# PowerDomains.net
KiCad netlist of a schematic drawn in Altium Designer
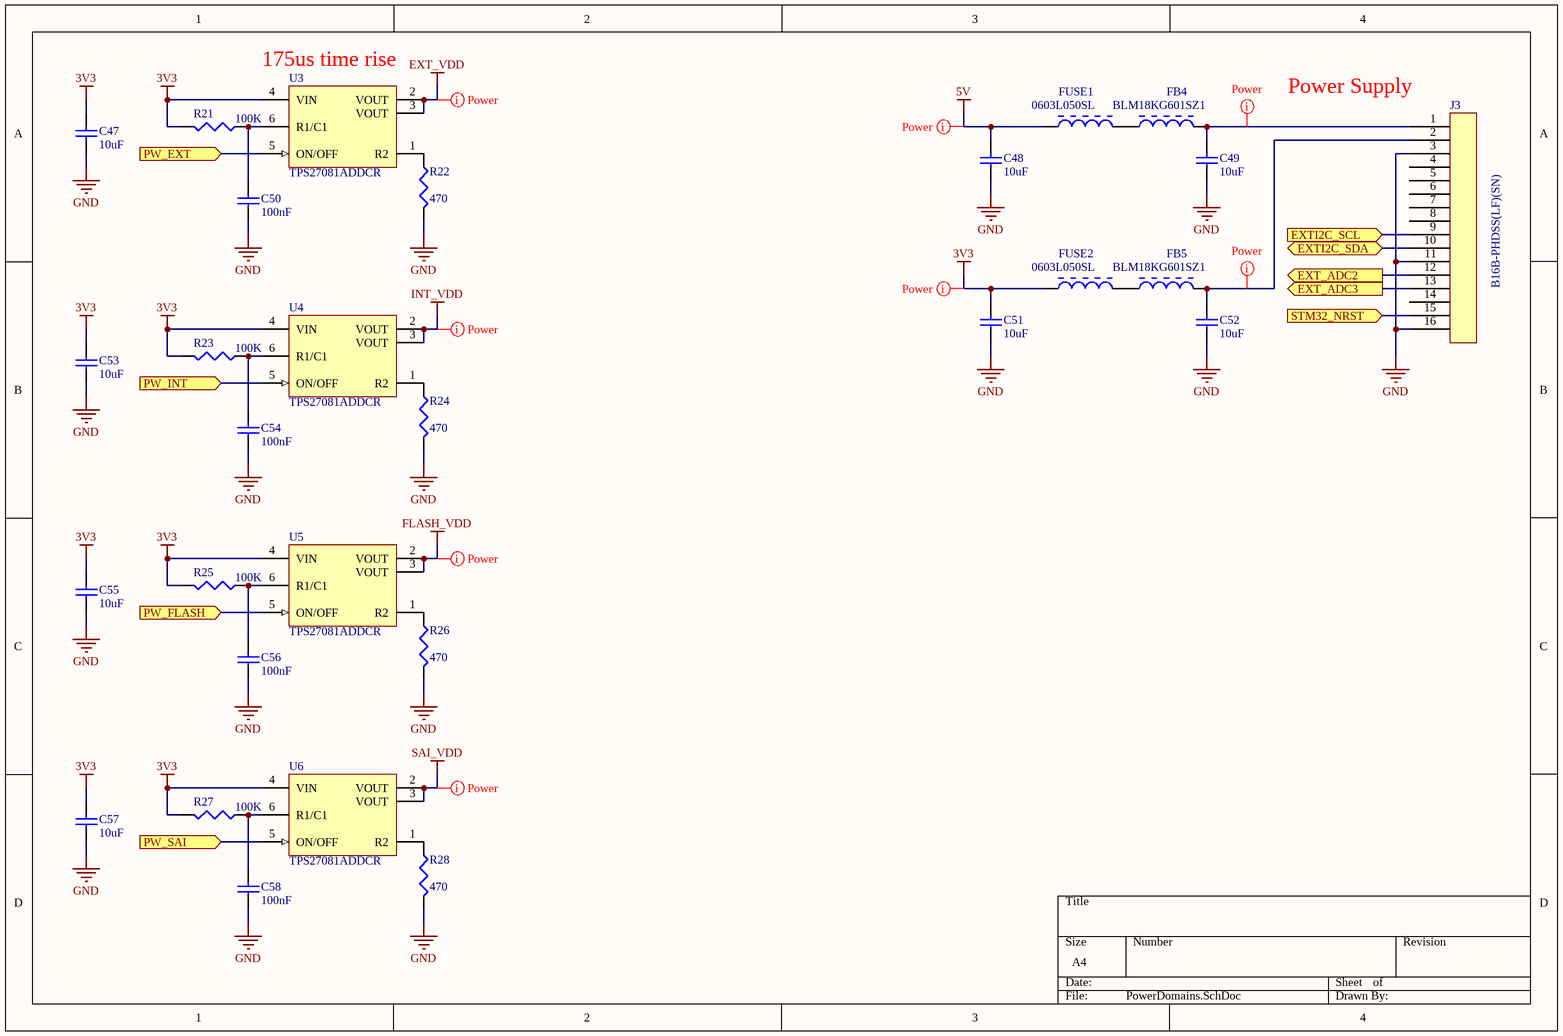
[diagram p0: PowerDomains.SchDoc]

(export (version "E")
  (design (tool "Eeschema 10.0.6"))
  (components
    (comp (ref "C47")
      (value "10uF")
      (footprint "CAPC1608X90X35NL10T15")
      (fields (field (name "PART NUMBER") "GRM188R71H102KA01D") (field (name "MANUFACTURER") "Murata"))
      (libsource (lib "Altium Content Vault") (part "CAP"))
    )
    (comp (ref "C48")
      (value "10uF")
      (footprint "CAPC1608X90X35NL10T15")
      (fields (field (name "PART NUMBER") "GRM188R71H102KA01D") (field (name "MANUFACTURER") "Murata"))
      (libsource (lib "Altium Content Vault") (part "CAP"))
    )
    (comp (ref "C49")
      (value "10uF")
      (footprint "CAPC1608X90X35NL10T15")
      (fields (field (name "PART NUMBER") "GRM188R71H102KA01D") (field (name "MANUFACTURER") "Murata"))
      (libsource (lib "Altium Content Vault") (part "CAP"))
    )
    (comp (ref "C50")
      (value "100nF")
      (footprint "CAPC1608X90X35NL10T15")
      (fields (field (name "PART NUMBER") "GRM188R71H102KA01D") (field (name "MANUFACTURER") "Murata"))
      (libsource (lib "Altium Content Vault") (part "CAP"))
    )
    (comp (ref "C51")
      (value "10uF")
      (footprint "CAPC1608X90X35NL10T15")
      (fields (field (name "PART NUMBER") "GRM188R71H102KA01D") (field (name "MANUFACTURER") "Murata"))
      (libsource (lib "Altium Content Vault") (part "CAP"))
    )
    (comp (ref "C52")
      (value "10uF")
      (footprint "CAPC1608X90X35NL10T15")
      (fields (field (name "PART NUMBER") "GRM188R71H102KA01D") (field (name "MANUFACTURER") "Murata"))
      (libsource (lib "Altium Content Vault") (part "CAP"))
    )
    (comp (ref "C53")
      (value "10uF")
      (footprint "CAPC1608X90X35NL10T15")
      (fields (field (name "PART NUMBER") "GRM188R71H102KA01D") (field (name "MANUFACTURER") "Murata"))
      (libsource (lib "Altium Content Vault") (part "CAP"))
    )
    (comp (ref "C54")
      (value "100nF")
      (footprint "CAPC1608X90X35NL10T15")
      (fields (field (name "PART NUMBER") "GRM188R71H102KA01D") (field (name "MANUFACTURER") "Murata"))
      (libsource (lib "Altium Content Vault") (part "CAP"))
    )
    (comp (ref "C55")
      (value "10uF")
      (footprint "CAPC1608X90X35NL10T15")
      (fields (field (name "PART NUMBER") "GRM188R71H102KA01D") (field (name "MANUFACTURER") "Murata"))
      (libsource (lib "Altium Content Vault") (part "CAP"))
    )
    (comp (ref "C56")
      (value "100nF")
      (footprint "CAPC1608X90X35NL10T15")
      (fields (field (name "PART NUMBER") "GRM188R71H102KA01D") (field (name "MANUFACTURER") "Murata"))
      (libsource (lib "Altium Content Vault") (part "CAP"))
    )
    (comp (ref "C57")
      (value "10uF")
      (footprint "CAPC1608X90X35NL10T15")
      (fields (field (name "PART NUMBER") "GRM188R71H102KA01D") (field (name "MANUFACTURER") "Murata"))
      (libsource (lib "Altium Content Vault") (part "CAP"))
    )
    (comp (ref "C58")
      (value "100nF")
      (footprint "CAPC1608X90X35NL10T15")
      (fields (field (name "PART NUMBER") "GRM188R71H102KA01D") (field (name "MANUFACTURER") "Murata"))
      (libsource (lib "Altium Content Vault") (part "CAP"))
    )
    (comp (ref "FB4")
      (value "BLM18KG601SZ1")
      (footprint "MURA-BLM18SG-B25-CHIP-2_V1")
      (fields (field (name "MANUFACTURER") "Murata") (field (name "PARTNUMBER") "BLM18SG221TN1D"))
      (libsource (lib "Altium Content Vault") (part "MURA-FB-2"))
    )
    (comp (ref "FB5")
      (value "BLM18KG601SZ1")
      (footprint "MURA-BLM18SG-B25-CHIP-2_V1")
      (fields (field (name "MANUFACTURER") "Murata") (field (name "PARTNUMBER") "BLM18SG221TN1D"))
      (libsource (lib "Altium Content Vault") (part "MURA-FB-2"))
    )
    (comp (ref "FUSE1")
      (value "0603L050SL")
      (footprint "MURA-BLM18SG-B25-CHIP-2_V1")
      (fields (field (name "MANUFACTURER") "Murata") (field (name "PARTNUMBER") "BLM18SG221TN1D"))
      (libsource (lib "Altium Content Vault") (part "MURA-FB-2"))
    )
    (comp (ref "FUSE2")
      (value "0603L050SL")
      (footprint "MURA-BLM18SG-B25-CHIP-2_V1")
      (fields (field (name "MANUFACTURER") "Murata") (field (name "PARTNUMBER") "BLM18SG221TN1D"))
      (libsource (lib "Altium Content Vault") (part "MURA-FB-2"))
    )
    (comp (ref "J3")
      (value "B16B-PHDSS(LF)(SN)")
      (footprint "B16B-PHDSS(LF)(SN) - duplicate")
      (libsource (lib "STM32WB55RGV7") (part "B16B-PHDSS(LF)(SN)"))
    )
    (comp (ref "R21")
      (value "100K")
      (footprint "J1-0603")
      (description "Resistor")
      (fields (field (name "PUBLISHER") "Altium Limited"))
      (libsource (lib "Miscellaneous Devices") (part "Res3"))
    )
    (comp (ref "R22")
      (value "470")
      (footprint "J1-0603")
      (description "Resistor")
      (fields (field (name "PUBLISHER") "Altium Limited"))
      (libsource (lib "Miscellaneous Devices") (part "Res3"))
    )
    (comp (ref "R23")
      (value "100K")
      (footprint "J1-0603")
      (description "Resistor")
      (fields (field (name "PUBLISHER") "Altium Limited"))
      (libsource (lib "Miscellaneous Devices") (part "Res3"))
    )
    (comp (ref "R24")
      (value "470")
      (footprint "J1-0603")
      (description "Resistor")
      (fields (field (name "PUBLISHER") "Altium Limited"))
      (libsource (lib "Miscellaneous Devices") (part "Res3"))
    )
    (comp (ref "R25")
      (value "100K")
      (footprint "J1-0603")
      (description "Resistor")
      (fields (field (name "PUBLISHER") "Altium Limited"))
      (libsource (lib "Miscellaneous Devices") (part "Res3"))
    )
    (comp (ref "R26")
      (value "470")
      (footprint "J1-0603")
      (description "Resistor")
      (fields (field (name "PUBLISHER") "Altium Limited"))
      (libsource (lib "Miscellaneous Devices") (part "Res3"))
    )
    (comp (ref "R27")
      (value "100K")
      (footprint "J1-0603")
      (description "Resistor")
      (fields (field (name "PUBLISHER") "Altium Limited"))
      (libsource (lib "Miscellaneous Devices") (part "Res3"))
    )
    (comp (ref "R28")
      (value "470")
      (footprint "J1-0603")
      (description "Resistor")
      (fields (field (name "PUBLISHER") "Altium Limited"))
      (libsource (lib "Miscellaneous Devices") (part "Res3"))
    )
    (comp (ref "U3")
      (value "TPS27081ADDCR")
      (footprint "DDC0006A_L")
      (fields (field (name "PARTNUMBER") "TPS27081A") (field (name "MANUFACTURER") "Texas Instruments"))
      (libsource (lib "Altium Content Vault") (part "TI-TPS27081A-DDC-6"))
    )
    (comp (ref "U4")
      (value "TPS27081ADDCR")
      (footprint "DDC0006A_L")
      (fields (field (name "PARTNUMBER") "TPS27081A") (field (name "MANUFACTURER") "Texas Instruments"))
      (libsource (lib "Altium Content Vault") (part "TI-TPS27081A-DDC-6"))
    )
    (comp (ref "U5")
      (value "TPS27081ADDCR")
      (footprint "DDC0006A_L")
      (fields (field (name "PARTNUMBER") "TPS27081A") (field (name "MANUFACTURER") "Texas Instruments"))
      (libsource (lib "Altium Content Vault") (part "TI-TPS27081A-DDC-6"))
    )
    (comp (ref "U6")
      (value "TPS27081ADDCR")
      (footprint "DDC0006A_L")
      (fields (field (name "PARTNUMBER") "TPS27081A") (field (name "MANUFACTURER") "Texas Instruments"))
      (libsource (lib "Altium Content Vault") (part "TI-TPS27081A-DDC-6"))
    )
  )
  (nets
    (net (code "1") (name "/EXTI2C_SCL") (class "Default") (node (ref "J3") (pin "9") (pintype "passive")))
    (net (code "2") (name "/EXTI2C_SDA") (class "Default") (node (ref "J3") (pin "10") (pintype "passive")))
    (net (code "3") (name "/EXT_ADC2") (class "Default") (node (ref "J3") (pin "12") (pintype "passive")))
    (net (code "4") (name "/EXT_ADC3") (class "Default") (node (ref "J3") (pin "13") (pintype "passive")))
    (net (code "5") (name "/PW_EXT") (class "Default")
      (node (ref "U3") (pin "5") (pinfunction "ON/OFF_5") (pintype "input"))
    )
    (net (code "6") (name "/PW_FLASH") (class "Default")
      (node (ref "U5") (pin "5") (pinfunction "ON/OFF_5") (pintype "input"))
    )
    (net (code "7") (name "/PW_INT") (class "Default")
      (node (ref "U4") (pin "5") (pinfunction "ON/OFF_5") (pintype "input"))
    )
    (net (code "8") (name "/PW_SAI") (class "Default")
      (node (ref "U6") (pin "5") (pinfunction "ON/OFF_5") (pintype "input"))
    )
    (net (code "9") (name "/STM32_NRST") (class "Default") (node (ref "J3") (pin "15") (pintype "passive")))
    (net (code "10") (name "3V3") (class "Default")
      (node (ref "C47") (pin "2") (pinfunction "2_2") (pintype "passive"))
      (node (ref "C51") (pin "2") (pinfunction "2_2") (pintype "passive"))
      (node (ref "C53") (pin "2") (pinfunction "2_2") (pintype "passive"))
      (node (ref "C55") (pin "2") (pinfunction "2_2") (pintype "passive"))
      (node (ref "C57") (pin "2") (pinfunction "2_2") (pintype "passive"))
      (node (ref "FUSE2") (pin "1") (pinfunction "1_1") (pintype "passive"))
      (node (ref "R21") (pin "2") (pinfunction "2_2") (pintype "passive"))
      (node (ref "R23") (pin "2") (pinfunction "2_2") (pintype "passive"))
      (node (ref "R25") (pin "2") (pinfunction "2_2") (pintype "passive"))
      (node (ref "R27") (pin "2") (pinfunction "2_2") (pintype "passive"))
      (node (ref "U3") (pin "4") (pinfunction "VIN_4") (pintype "power_in"))
      (node (ref "U4") (pin "4") (pinfunction "VIN_4") (pintype "power_in"))
      (node (ref "U5") (pin "4") (pinfunction "VIN_4") (pintype "power_in"))
      (node (ref "U6") (pin "4") (pinfunction "VIN_4") (pintype "power_in"))
    )
    (net (code "11") (name "5V") (class "Default")
      (node (ref "C48") (pin "2") (pinfunction "2_2") (pintype "passive"))
      (node (ref "FUSE1") (pin "1") (pinfunction "1_1") (pintype "passive"))
    )
    (net (code "12") (name "EXT_VDD") (class "Default")
      (node (ref "U3") (pin "2") (pinfunction "VOUT_2") (pintype "power_in"))
      (node (ref "U3") (pin "3") (pinfunction "VOUT_3") (pintype "power_in"))
    )
    (net (code "13") (name "FLASH_VDD") (class "Default")
      (node (ref "U5") (pin "2") (pinfunction "VOUT_2") (pintype "power_in"))
      (node (ref "U5") (pin "3") (pinfunction "VOUT_3") (pintype "power_in"))
    )
    (net (code "14") (name "GND") (class "Default")
      (node (ref "C47") (pin "1") (pinfunction "1_1") (pintype "passive"))
      (node (ref "C48") (pin "1") (pinfunction "1_1") (pintype "passive"))
      (node (ref "C49") (pin "1") (pinfunction "1_1") (pintype "passive"))
      (node (ref "C50") (pin "1") (pinfunction "1_1") (pintype "passive"))
      (node (ref "C51") (pin "1") (pinfunction "1_1") (pintype "passive"))
      (node (ref "C52") (pin "1") (pinfunction "1_1") (pintype "passive"))
      (node (ref "C53") (pin "1") (pinfunction "1_1") (pintype "passive"))
      (node (ref "C54") (pin "1") (pinfunction "1_1") (pintype "passive"))
      (node (ref "C55") (pin "1") (pinfunction "1_1") (pintype "passive"))
      (node (ref "C56") (pin "1") (pinfunction "1_1") (pintype "passive"))
      (node (ref "C57") (pin "1") (pinfunction "1_1") (pintype "passive"))
      (node (ref "C58") (pin "1") (pinfunction "1_1") (pintype "passive"))
      (node (ref "J3") (pin "11") (pintype "passive"))
      (node (ref "J3") (pin "16") (pintype "passive"))
      (node (ref "J3") (pin "3") (pintype "passive"))
      (node (ref "R22") (pin "2") (pinfunction "2_2") (pintype "passive"))
      (node (ref "R24") (pin "2") (pinfunction "2_2") (pintype "passive"))
      (node (ref "R26") (pin "2") (pinfunction "2_2") (pintype "passive"))
      (node (ref "R28") (pin "2") (pinfunction "2_2") (pintype "passive"))
    )
    (net (code "15") (name "INT_VDD") (class "Default")
      (node (ref "U4") (pin "2") (pinfunction "VOUT_2") (pintype "power_in"))
      (node (ref "U4") (pin "3") (pinfunction "VOUT_3") (pintype "power_in"))
    )
    (net (code "16") (name "Net-(C49-Pad2)") (class "Default")
      (node (ref "C49") (pin "2") (pinfunction "2_2") (pintype "passive"))
      (node (ref "FB4") (pin "2") (pinfunction "2_2") (pintype "passive"))
      (node (ref "J3") (pin "1") (pintype "passive"))
    )
    (net (code "17") (name "Net-(C52-Pad2)") (class "Default")
      (node (ref "C52") (pin "2") (pinfunction "2_2") (pintype "passive"))
      (node (ref "FB5") (pin "2") (pinfunction "2_2") (pintype "passive"))
      (node (ref "J3") (pin "2") (pintype "passive"))
    )
    (net (code "18") (name "Net-(FB4-Pad1)") (class "Default")
      (node (ref "FB4") (pin "1") (pinfunction "1_1") (pintype "passive"))
      (node (ref "FUSE1") (pin "2") (pinfunction "2_2") (pintype "passive"))
    )
    (net (code "19") (name "Net-(FB5-Pad1)") (class "Default")
      (node (ref "FB5") (pin "1") (pinfunction "1_1") (pintype "passive"))
      (node (ref "FUSE2") (pin "2") (pinfunction "2_2") (pintype "passive"))
    )
    (net (code "20") (name "Net-(U3-R1{slash}C1)") (class "Default")
      (node (ref "C50") (pin "2") (pinfunction "2_2") (pintype "passive"))
      (node (ref "R21") (pin "1") (pinfunction "1_1") (pintype "passive"))
      (node (ref "U3") (pin "6") (pinfunction "R1/C1_6") (pintype "passive"))
    )
    (net (code "21") (name "Net-(U3-R2)") (class "Default")
      (node (ref "R22") (pin "1") (pinfunction "1_1") (pintype "passive"))
      (node (ref "U3") (pin "1") (pinfunction "R2_1") (pintype "passive"))
    )
    (net (code "22") (name "Net-(U4-R1{slash}C1)") (class "Default")
      (node (ref "C54") (pin "2") (pinfunction "2_2") (pintype "passive"))
      (node (ref "R23") (pin "1") (pinfunction "1_1") (pintype "passive"))
      (node (ref "U4") (pin "6") (pinfunction "R1/C1_6") (pintype "passive"))
    )
    (net (code "23") (name "Net-(U4-R2)") (class "Default")
      (node (ref "R24") (pin "1") (pinfunction "1_1") (pintype "passive"))
      (node (ref "U4") (pin "1") (pinfunction "R2_1") (pintype "passive"))
    )
    (net (code "24") (name "Net-(U5-R1{slash}C1)") (class "Default")
      (node (ref "C56") (pin "2") (pinfunction "2_2") (pintype "passive"))
      (node (ref "R25") (pin "1") (pinfunction "1_1") (pintype "passive"))
      (node (ref "U5") (pin "6") (pinfunction "R1/C1_6") (pintype "passive"))
    )
    (net (code "25") (name "Net-(U5-R2)") (class "Default")
      (node (ref "R26") (pin "1") (pinfunction "1_1") (pintype "passive"))
      (node (ref "U5") (pin "1") (pinfunction "R2_1") (pintype "passive"))
    )
    (net (code "26") (name "Net-(U6-R1{slash}C1)") (class "Default")
      (node (ref "C58") (pin "2") (pinfunction "2_2") (pintype "passive"))
      (node (ref "R27") (pin "1") (pinfunction "1_1") (pintype "passive"))
      (node (ref "U6") (pin "6") (pinfunction "R1/C1_6") (pintype "passive"))
    )
    (net (code "27") (name "Net-(U6-R2)") (class "Default")
      (node (ref "R28") (pin "1") (pinfunction "1_1") (pintype "passive"))
      (node (ref "U6") (pin "1") (pinfunction "R2_1") (pintype "passive"))
    )
    (net (code "28") (name "SAI_VDD") (class "Default")
      (node (ref "U6") (pin "2") (pinfunction "VOUT_2") (pintype "power_in"))
      (node (ref "U6") (pin "3") (pinfunction "VOUT_3") (pintype "power_in"))
    )
    (net (code "29") (name "unconnected-(J3-Pad4)") (class "Default")
      (node (ref "J3") (pin "4") (pintype "passive"))
    )
    (net (code "30") (name "unconnected-(J3-Pad5)") (class "Default")
      (node (ref "J3") (pin "5") (pintype "passive"))
    )
    (net (code "31") (name "unconnected-(J3-Pad6)") (class "Default")
      (node (ref "J3") (pin "6") (pintype "passive"))
    )
    (net (code "32") (name "unconnected-(J3-Pad7)") (class "Default")
      (node (ref "J3") (pin "7") (pintype "passive"))
    )
    (net (code "33") (name "unconnected-(J3-Pad8)") (class "Default")
      (node (ref "J3") (pin "8") (pintype "passive"))
    )
    (net (code "34") (name "unconnected-(J3-Pad14)") (class "Default")
      (node (ref "J3") (pin "14") (pintype "passive"))
    )
  )
)
